# 06_MCU.net
KiCad netlist of a schematic drawn in Altium Designer
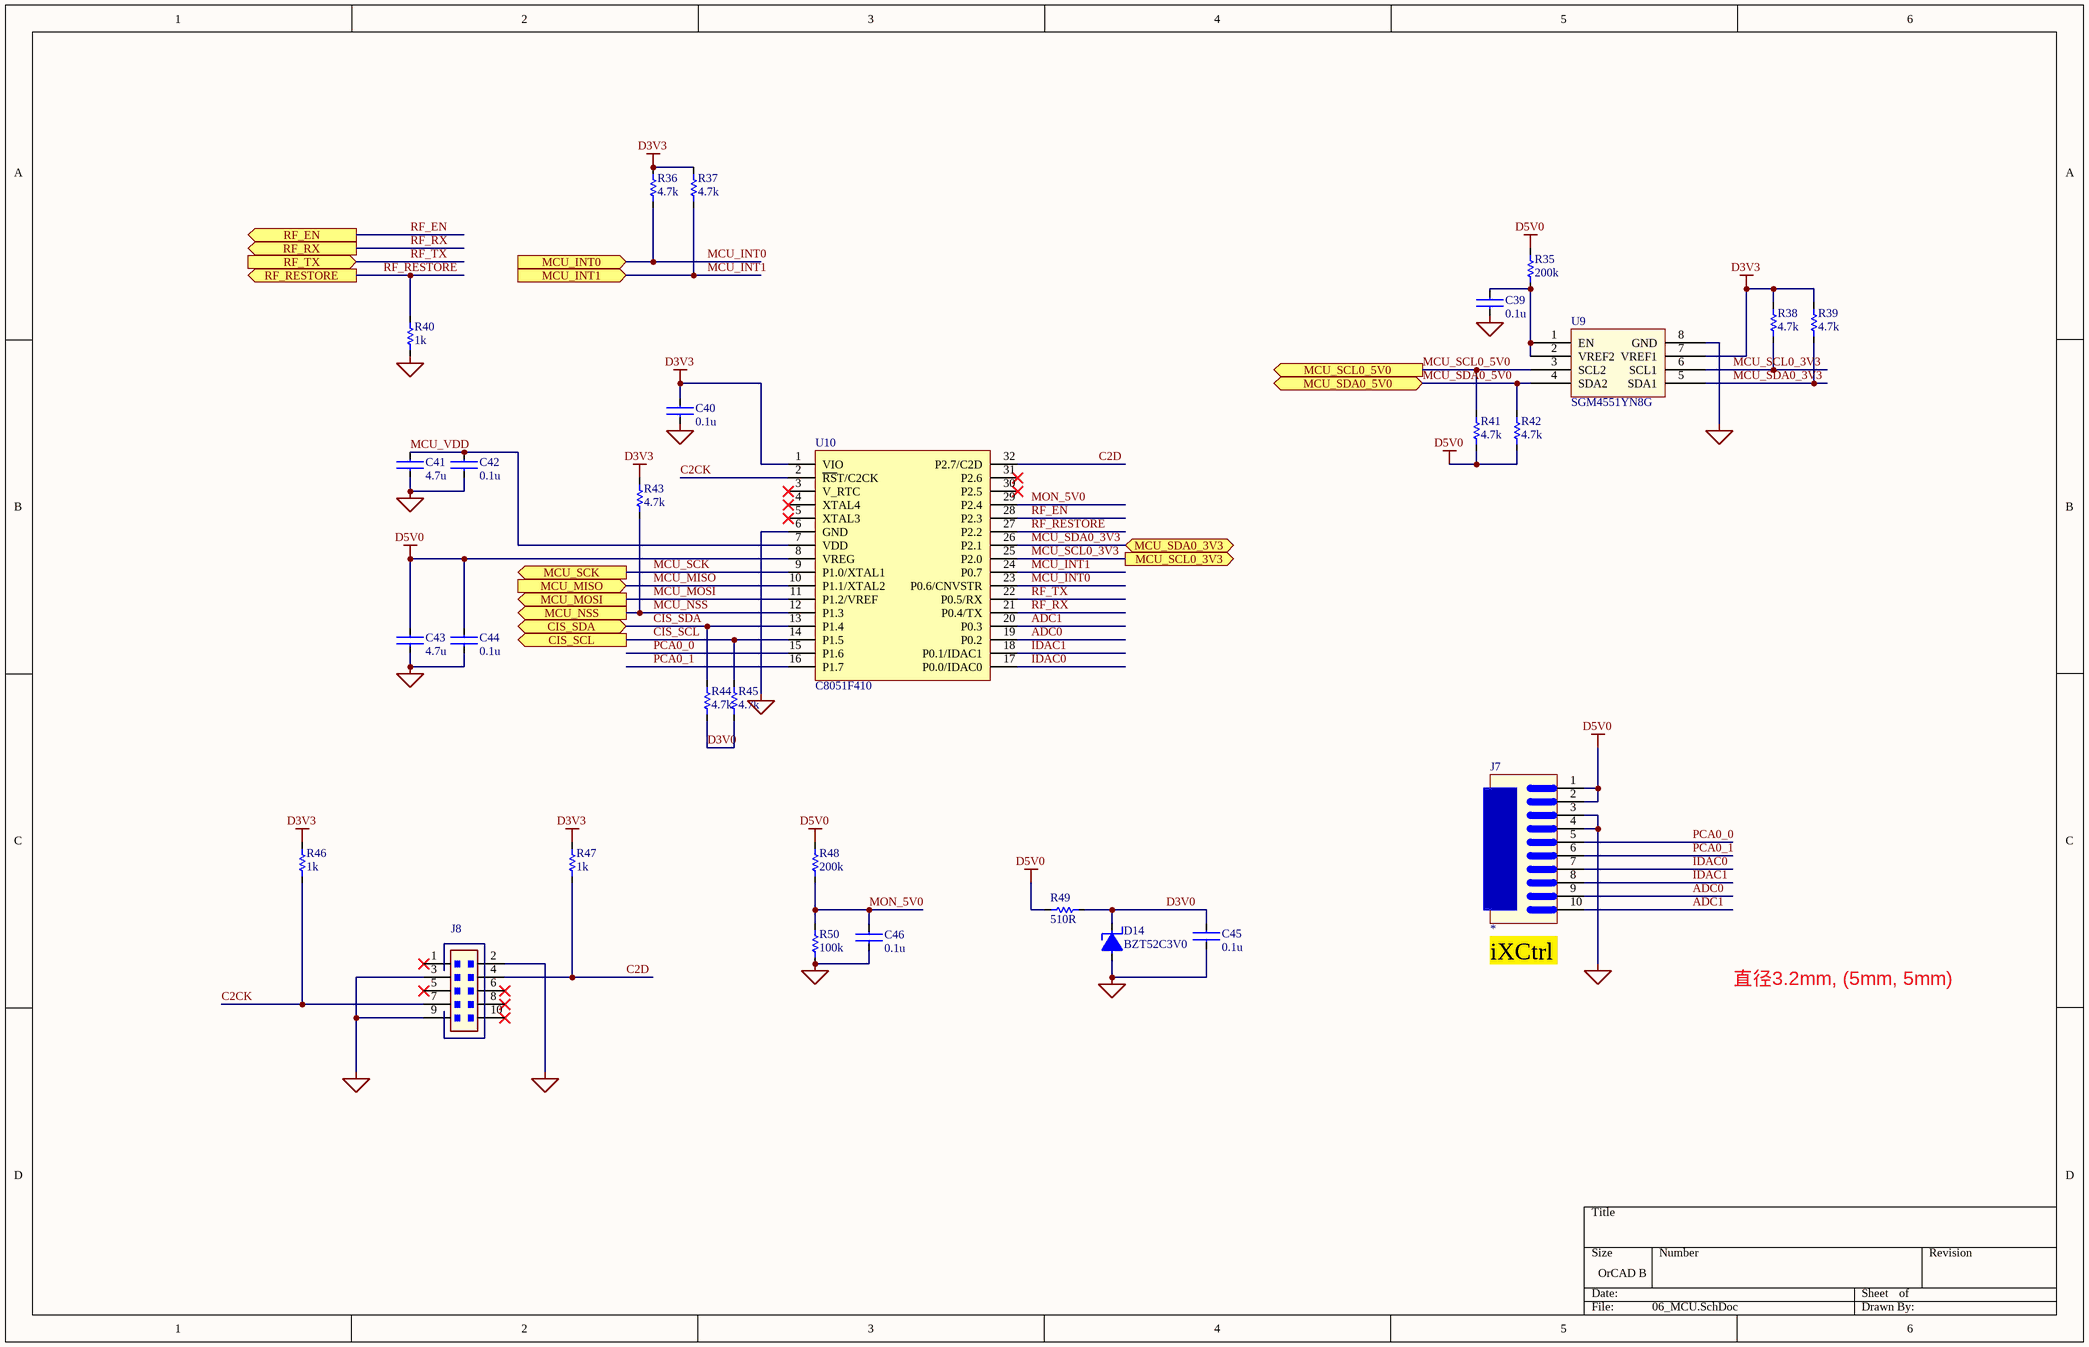
[diagram p0: 06_MCU.SchDoc]

(export (version "E")
  (design (tool "Eeschema 10.0.6"))
  (components
    (comp (ref "C39")
      (value "0.1u")
      (footprint "C0402")
      (description "CAP,Ceramic,X7R,10%,16V,0.1uF,0402")
      (libsource (lib "C0402") (part "CAP011"))
    )
    (comp (ref "C40")
      (value "0.1u")
      (footprint "C0402")
      (description "CAP,Ceramic,X7R,10%,16V,0.1uF,0402")
      (libsource (lib "C0402") (part "CAP011"))
    )
    (comp (ref "C41")
      (value "4.7u")
      (footprint "CAPC1608X09N_C0603")
      (description "CAP,Ceramic,X5R,10%,6.3V,4.7uF,0603")
      (libsource (lib "AD15_libpkg") (part "CAP17"))
    )
    (comp (ref "C42")
      (value "0.1u")
      (footprint "C0402")
      (description "CAP,Ceramic,X7R,10%,16V,0.1uF,0402")
      (libsource (lib "C0402") (part "CAP011"))
    )
    (comp (ref "C43")
      (value "4.7u")
      (footprint "CAPC1608X09N_C0603")
      (description "CAP,Ceramic,X5R,10%,6.3V,4.7uF,0603")
      (libsource (lib "AD15_libpkg") (part "CAP17"))
    )
    (comp (ref "C44")
      (value "0.1u")
      (footprint "C0402")
      (description "CAP,Ceramic,X7R,10%,16V,0.1uF,0402")
      (libsource (lib "C0402") (part "CAP011"))
    )
    (comp (ref "C45")
      (value "0.1u")
      (footprint "C0402")
      (description "CAP,Ceramic,X7R,10%,16V,0.1uF,0402")
      (libsource (lib "C0402") (part "CAP011"))
    )
    (comp (ref "C46")
      (value "0.1u")
      (footprint "C0402")
      (description "CAP,Ceramic,X7R,10%,16V,0.1uF,0402")
      (libsource (lib "C0402") (part "CAP011"))
    )
    (comp (ref "D14")
      (value "BZT52C3V0")
      (footprint "SODFL370X10-2N_SOD123_BZT52C")
      (description "Zener Diodes,3.0V,5mA,2%,SOD123")
      (libsource (lib "AD15_libpkg") (part "BZT52C3V0"))
    )
    (comp (ref "J7")
      (value "*")
      (footprint "FPC0.5mm-10pin")
      (description "FFC socket,10-Pin,bottom contact,0.5mm Pitch,SMD")
      (libsource (lib "AD15_schlib") (part "FPC0.5mm_06"))
    )
    (comp (ref "J8")
      (value "JTAG")
      (footprint "3011001XXX00")
      (description "Header,10Pin,Vertical,2.54mm Pitch,TH")
      (libsource (lib "AD15_schlib") (part "3011001XXX00"))
    )
    (comp (ref "R35")
      (value "200k")
      (footprint "R0402")
      (description "RES,200k,1%,1/16W,0402")
      (libsource (lib "R0402") (part "RES0117"))
    )
    (comp (ref "R36")
      (value "4.7k")
      (footprint "R0402")
      (description "RES,4.7k,1%,1/16W,0402")
      (libsource (lib "R0402") (part "RES015"))
    )
    (comp (ref "R37")
      (value "4.7k")
      (footprint "R0402")
      (description "RES,4.7k,1%,1/16W,0402")
      (libsource (lib "R0402") (part "RES015"))
    )
    (comp (ref "R38")
      (value "4.7k")
      (footprint "R0402")
      (description "RES,4.7k,1%,1/16W,0402")
      (libsource (lib "R0402") (part "RES015"))
    )
    (comp (ref "R39")
      (value "4.7k")
      (footprint "R0402")
      (description "RES,4.7k,1%,1/16W,0402")
      (libsource (lib "R0402") (part "RES015"))
    )
    (comp (ref "R40")
      (value "1k")
      (footprint "R0402")
      (description "RES,1k,1%,1/16W,0402")
      (libsource (lib "R0402") (part "RES011"))
    )
    (comp (ref "R41")
      (value "4.7k")
      (footprint "R0402")
      (description "RES,4.7k,1%,1/16W,0402")
      (libsource (lib "R0402") (part "RES015"))
    )
    (comp (ref "R42")
      (value "4.7k")
      (footprint "R0402")
      (description "RES,4.7k,1%,1/16W,0402")
      (libsource (lib "R0402") (part "RES015"))
    )
    (comp (ref "R43")
      (value "4.7k")
      (footprint "R0402")
      (description "RES,4.7k,1%,1/16W,0402")
      (libsource (lib "R0402") (part "RES015"))
    )
    (comp (ref "R44")
      (value "4.7k")
      (footprint "R0402")
      (description "RES,4.7k,1%,1/16W,0402")
      (libsource (lib "R0402") (part "RES015"))
    )
    (comp (ref "R45")
      (value "4.7k")
      (footprint "R0402")
      (description "RES,4.7k,1%,1/16W,0402")
      (libsource (lib "R0402") (part "RES015"))
    )
    (comp (ref "R46")
      (value "1k")
      (footprint "R0402")
      (description "RES,1k,1%,1/16W,0402")
      (libsource (lib "R0402") (part "RES011"))
    )
    (comp (ref "R47")
      (value "1k")
      (footprint "R0402")
      (description "RES,1k,1%,1/16W,0402")
      (libsource (lib "R0402") (part "RES011"))
    )
    (comp (ref "R48")
      (value "200k")
      (footprint "R0402")
      (description "RES,200k,1%,1/16W,0402")
      (libsource (lib "R0402") (part "RES0117"))
    )
    (comp (ref "R49")
      (value "510R")
      (footprint "R0402")
      (description "RES,510R,1%,1/16W,0402")
      (libsource (lib "R0402") (part "RES0128"))
    )
    (comp (ref "R50")
      (value "100k")
      (footprint "R0402")
      (description "RES,100k,1%,1/16W,0402")
      (libsource (lib "R0402") (part "RES013"))
    )
    (comp (ref "U9")
      (value "SGM4551YN8G")
      (footprint "TSOP65P280X125-8N_SGM4551")
      (description "IC,I2C-bus and SMBus voltage-level translator,SOT23-8")
      (libsource (lib "AD15_libpkg") (part "SGM4551YN8G"))
    )
    (comp (ref "U10")
      (value "C8051F410")
      (footprint "TQFP80P900X900X160-32N")
      (description "IC,MCU,50MIPS,32K FLASH,12bits ADC,TQFP32")
      (libsource (lib "AD15_Silabs_schlib") (part "C8051F410"))
    )
  )
  (nets
    (net (code "1") (name "/ADC0") (class "Default")
      (node (ref "J7") (pin "9") (pinfunction "8_9") (pintype "passive"))
      (node (ref "U10") (pin "19") (pinfunction "P0.2_19") (pintype "passive"))
    )
    (net (code "2") (name "/ADC1") (class "Default")
      (node (ref "J7") (pin "10") (pinfunction "9_10") (pintype "passive"))
      (node (ref "U10") (pin "20") (pinfunction "P0.3_20") (pintype "passive"))
    )
    (net (code "3") (name "/C2CK") (class "Default")
      (node (ref "J8") (pin "7") (pinfunction "7_7") (pintype "passive"))
      (node (ref "R46") (pin "1") (pinfunction "0_1") (pintype "passive"))
      (node (ref "U10") (pin "2") (pinfunction "~{RS}T/C2CK_2") (pintype "passive"))
    )
    (net (code "4") (name "/C2D") (class "Default")
      (node (ref "J8") (pin "4") (pinfunction "3_4") (pintype "passive"))
      (node (ref "R47") (pin "1") (pinfunction "0_1") (pintype "passive"))
      (node (ref "U10") (pin "32") (pinfunction "P2.7/C2D_32") (pintype "passive"))
    )
    (net (code "5") (name "/CIS_SCL") (class "Default")
      (node (ref "R45") (pin "2") (pinfunction "2_2") (pintype "passive"))
      (node (ref "U10") (pin "14") (pinfunction "P1.5_14") (pintype "passive"))
    )
    (net (code "6") (name "/CIS_SDA") (class "Default")
      (node (ref "R44") (pin "2") (pinfunction "2_2") (pintype "passive"))
      (node (ref "U10") (pin "13") (pinfunction "P1.4_13") (pintype "passive"))
    )
    (net (code "7") (name "/D3V0") (class "Default")
      (node (ref "C45") (pin "1") (pinfunction "0_1") (pintype "passive"))
      (node (ref "D14") (pin "2") (pinfunction "K_2") (pintype "passive"))
      (node (ref "R44") (pin "1") (pinfunction "0_1") (pintype "passive"))
      (node (ref "R45") (pin "1") (pinfunction "0_1") (pintype "passive"))
      (node (ref "R49") (pin "2") (pinfunction "2_2") (pintype "passive"))
    )
    (net (code "8") (name "/IDAC0") (class "Default")
      (node (ref "J7") (pin "7") (pinfunction "6_7") (pintype "passive"))
      (node (ref "U10") (pin "17") (pinfunction "P0.0/IDAC0_17") (pintype "passive"))
    )
    (net (code "9") (name "/IDAC1") (class "Default")
      (node (ref "J7") (pin "8") (pinfunction "7_8") (pintype "passive"))
      (node (ref "U10") (pin "18") (pinfunction "P0.1/IDAC1_18") (pintype "passive"))
    )
    (net (code "10") (name "/MCU_INT0") (class "Default")
      (node (ref "R36") (pin "1") (pinfunction "0_1") (pintype "passive"))
      (node (ref "U10") (pin "23") (pinfunction "P0.6/CNVSTR_23") (pintype "passive"))
    )
    (net (code "11") (name "/MCU_INT1") (class "Default")
      (node (ref "R37") (pin "1") (pinfunction "0_1") (pintype "passive"))
      (node (ref "U10") (pin "24") (pinfunction "P0.7_24") (pintype "passive"))
    )
    (net (code "12") (name "/MCU_MISO") (class "Default")
      (node (ref "U10") (pin "10") (pinfunction "P1.1/XTAL2_10") (pintype "passive"))
    )
    (net (code "13") (name "/MCU_MOSI") (class "Default")
      (node (ref "U10") (pin "11") (pinfunction "P1.2/VREF_11") (pintype "passive"))
    )
    (net (code "14") (name "/MCU_NSS") (class "Default")
      (node (ref "R43") (pin "1") (pinfunction "0_1") (pintype "passive"))
      (node (ref "U10") (pin "12") (pinfunction "P1.3_12") (pintype "passive"))
    )
    (net (code "15") (name "/MCU_SCK") (class "Default")
      (node (ref "U10") (pin "9") (pinfunction "P1.0/XTAL1_9") (pintype "passive"))
    )
    (net (code "16") (name "/MCU_SCL0_3V3") (class "Default")
      (node (ref "R38") (pin "1") (pinfunction "0_1") (pintype "passive"))
      (node (ref "U10") (pin "25") (pinfunction "P2.0_25") (pintype "passive"))
      (node (ref "U9") (pin "6") (pinfunction "SCL1_6") (pintype "passive"))
    )
    (net (code "17") (name "/MCU_SCL0_5V0") (class "Default")
      (node (ref "R41") (pin "2") (pinfunction "2_2") (pintype "passive"))
      (node (ref "U9") (pin "3") (pinfunction "SCL2_3") (pintype "passive"))
    )
    (net (code "18") (name "/MCU_SDA0_3V3") (class "Default")
      (node (ref "R39") (pin "1") (pinfunction "0_1") (pintype "passive"))
      (node (ref "U10") (pin "26") (pinfunction "P2.1_26") (pintype "passive"))
      (node (ref "U9") (pin "5") (pinfunction "SDA1_5") (pintype "passive"))
    )
    (net (code "19") (name "/MCU_SDA0_5V0") (class "Default")
      (node (ref "R42") (pin "2") (pinfunction "2_2") (pintype "passive"))
      (node (ref "U9") (pin "4") (pinfunction "SDA2_4") (pintype "passive"))
    )
    (net (code "20") (name "/MCU_VDD") (class "Default")
      (node (ref "C41") (pin "1") (pinfunction "0_1") (pintype "passive"))
      (node (ref "C42") (pin "1") (pinfunction "0_1") (pintype "passive"))
      (node (ref "U10") (pin "7") (pinfunction "VDD_7") (pintype "passive"))
    )
    (net (code "21") (name "/MON_5V0") (class "Default")
      (node (ref "C46") (pin "1") (pinfunction "0_1") (pintype "passive"))
      (node (ref "R48") (pin "1") (pinfunction "0_1") (pintype "passive"))
      (node (ref "R50") (pin "2") (pinfunction "2_2") (pintype "passive"))
      (node (ref "U10") (pin "29") (pinfunction "P2.4_29") (pintype "passive"))
    )
    (net (code "22") (name "/PCA0_0") (class "Default")
      (node (ref "J7") (pin "5") (pinfunction "4_5") (pintype "passive"))
      (node (ref "U10") (pin "15") (pinfunction "P1.6_15") (pintype "passive"))
    )
    (net (code "23") (name "/PCA0_1") (class "Default")
      (node (ref "J7") (pin "6") (pinfunction "5_6") (pintype "passive"))
      (node (ref "U10") (pin "16") (pinfunction "P1.7_16") (pintype "passive"))
    )
    (net (code "24") (name "/RF_EN") (class "Default")
      (node (ref "U10") (pin "28") (pinfunction "P2.3_28") (pintype "passive"))
    )
    (net (code "25") (name "/RF_RESTORE") (class "Default")
      (node (ref "R40") (pin "2") (pinfunction "2_2") (pintype "passive"))
      (node (ref "U10") (pin "27") (pinfunction "P2.2_27") (pintype "passive"))
    )
    (net (code "26") (name "/RF_RX") (class "Default")
      (node (ref "U10") (pin "21") (pinfunction "P0.4/TX_21") (pintype "passive"))
    )
    (net (code "27") (name "/RF_TX") (class "Default")
      (node (ref "U10") (pin "22") (pinfunction "P0.5/RX_22") (pintype "passive"))
    )
    (net (code "28") (name "D3V3") (class "Default")
      (node (ref "C40") (pin "1") (pinfunction "0_1") (pintype "passive"))
      (node (ref "R36") (pin "2") (pinfunction "2_2") (pintype "passive"))
      (node (ref "R37") (pin "2") (pinfunction "2_2") (pintype "passive"))
      (node (ref "R38") (pin "2") (pinfunction "2_2") (pintype "passive"))
      (node (ref "R39") (pin "2") (pinfunction "2_2") (pintype "passive"))
      (node (ref "R43") (pin "2") (pinfunction "2_2") (pintype "passive"))
      (node (ref "R46") (pin "2") (pinfunction "2_2") (pintype "passive"))
      (node (ref "R47") (pin "2") (pinfunction "2_2") (pintype "passive"))
      (node (ref "U10") (pin "1") (pinfunction "VIO_1") (pintype "passive"))
      (node (ref "U9") (pin "7") (pinfunction "VREF1_7") (pintype "passive"))
    )
    (net (code "29") (name "D5V0") (class "Default")
      (node (ref "C43") (pin "1") (pinfunction "0_1") (pintype "passive"))
      (node (ref "C44") (pin "1") (pinfunction "0_1") (pintype "passive"))
      (node (ref "J7") (pin "1") (pinfunction "0_1") (pintype "passive"))
      (node (ref "J7") (pin "2") (pinfunction "1_2") (pintype "passive"))
      (node (ref "R35") (pin "2") (pinfunction "2_2") (pintype "passive"))
      (node (ref "R41") (pin "1") (pinfunction "0_1") (pintype "passive"))
      (node (ref "R42") (pin "1") (pinfunction "0_1") (pintype "passive"))
      (node (ref "R48") (pin "2") (pinfunction "2_2") (pintype "passive"))
      (node (ref "R49") (pin "1") (pinfunction "0_1") (pintype "passive"))
      (node (ref "U10") (pin "8") (pinfunction "VREG_8") (pintype "passive"))
    )
    (net (code "30") (name "GND") (class "Default")
      (node (ref "C39") (pin "2") (pinfunction "1_2") (pintype "passive"))
      (node (ref "C40") (pin "2") (pinfunction "1_2") (pintype "passive"))
      (node (ref "C41") (pin "2") (pinfunction "1_2") (pintype "passive"))
      (node (ref "C42") (pin "2") (pinfunction "1_2") (pintype "passive"))
      (node (ref "C43") (pin "2") (pinfunction "1_2") (pintype "passive"))
      (node (ref "C44") (pin "2") (pinfunction "1_2") (pintype "passive"))
      (node (ref "C45") (pin "2") (pinfunction "1_2") (pintype "passive"))
      (node (ref "C46") (pin "2") (pinfunction "1_2") (pintype "passive"))
      (node (ref "D14") (pin "1") (pinfunction "A_1") (pintype "passive"))
      (node (ref "J7") (pin "3") (pinfunction "2_3") (pintype "passive"))
      (node (ref "J7") (pin "4") (pinfunction "3_4") (pintype "passive"))
      (node (ref "J8") (pin "2") (pinfunction "1_2") (pintype "passive"))
      (node (ref "J8") (pin "3") (pinfunction "2_3") (pintype "passive"))
      (node (ref "J8") (pin "9") (pinfunction "9_9") (pintype "passive"))
      (node (ref "R40") (pin "1") (pinfunction "0_1") (pintype "passive"))
      (node (ref "R50") (pin "1") (pinfunction "0_1") (pintype "passive"))
      (node (ref "U10") (pin "6") (pinfunction "GND_6") (pintype "passive"))
      (node (ref "U9") (pin "8") (pinfunction "GND_8") (pintype "passive"))
    )
    (net (code "31") (name "Net-(C39-0)") (class "Default")
      (node (ref "C39") (pin "1") (pinfunction "0_1") (pintype "passive"))
      (node (ref "R35") (pin "1") (pinfunction "0_1") (pintype "passive"))
      (node (ref "U9") (pin "1") (pinfunction "EN_1") (pintype "passive"))
      (node (ref "U9") (pin "2") (pinfunction "VREF2_2") (pintype "passive"))
    )
    (net (code "32") (name "unconnected-(J8-0-Pad1)") (class "Default")
      (node (ref "J8") (pin "1") (pinfunction "0_1") (pintype "passive+no_connect"))
    )
    (net (code "33") (name "unconnected-(J8-4-Pad5)") (class "Default")
      (node (ref "J8") (pin "5") (pinfunction "4_5") (pintype "passive+no_connect"))
    )
    (net (code "34") (name "unconnected-(J8-5-Pad6)") (class "Default")
      (node (ref "J8") (pin "6") (pinfunction "5_6") (pintype "passive+no_connect"))
    )
    (net (code "35") (name "unconnected-(J8-9-Pad10)") (class "Default")
      (node (ref "J8") (pin "10") (pinfunction "9_10") (pintype "passive+no_connect"))
    )
    (net (code "36") (name "unconnected-(J8-Pad8)") (class "Default")
      (node (ref "J8") (pin "8") (pinfunction "8_8") (pintype "passive+no_connect"))
    )
    (net (code "37") (name "unconnected-(U10-P2.5-Pad30)") (class "Default")
      (node (ref "U10") (pin "30") (pinfunction "P2.5_30") (pintype "passive+no_connect"))
    )
    (net (code "38") (name "unconnected-(U10-P2.6-Pad31)") (class "Default")
      (node (ref "U10") (pin "31") (pinfunction "P2.6_31") (pintype "passive+no_connect"))
    )
    (net (code "39") (name "unconnected-(U10-V_RTC-Pad3)") (class "Default")
      (node (ref "U10") (pin "3") (pinfunction "V_RTC_3") (pintype "passive+no_connect"))
    )
    (net (code "40") (name "unconnected-(U10-XTAL3-Pad5)") (class "Default")
      (node (ref "U10") (pin "5") (pinfunction "XTAL3_5") (pintype "passive+no_connect"))
    )
    (net (code "41") (name "unconnected-(U10-XTAL4-Pad4)") (class "Default")
      (node (ref "U10") (pin "4") (pinfunction "XTAL4_4") (pintype "passive+no_connect"))
    )
  )
)
